# QCopterFC_MCU_Sch.net
KiCad netlist of a schematic drawn in Altium Designer
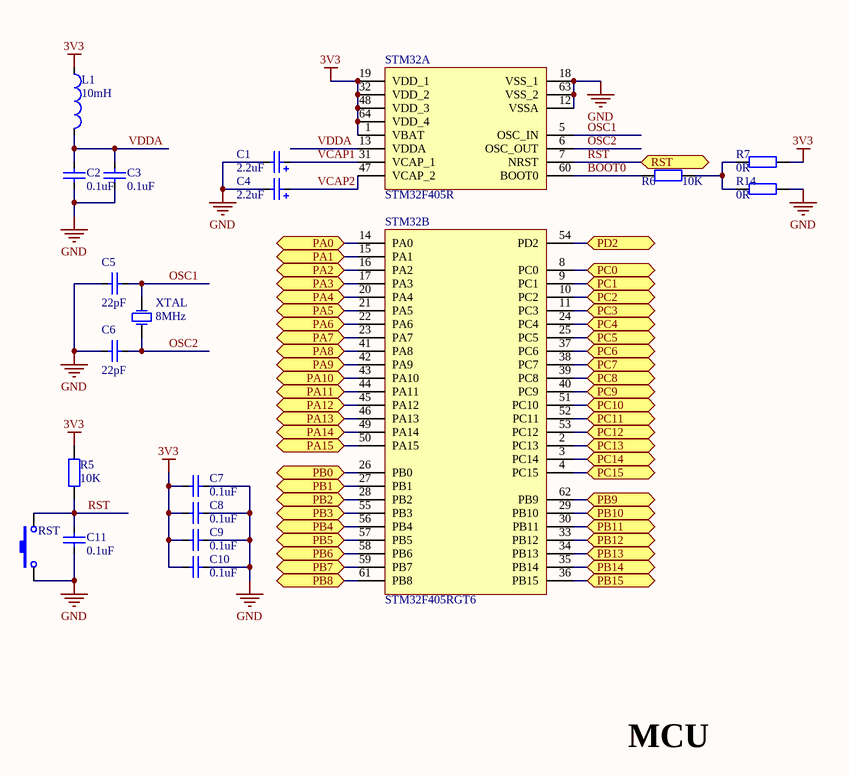
[diagram p0: QCopterFC_MCU_Sch.SchDoc]

(export (version "E")
  (design (tool "Eeschema 10.0.6"))
  (components
    (comp (ref "C1")
      (value "2.2uF")
      (footprint "PCB_Passive:CAP_TAN_P0805")
      (description "Capacitor")
      (fields (field (name "Comment") "Cap_Tan_0805"))
      (libsource (lib "SCH_Passive") (part "Cap_Tan_0805"))
    )
    (comp (ref "C2")
      (value "0.1uF")
      (footprint "PCB_Passive:CAP_0603")
      (description "Capacitor")
      (fields (field (name "Comment") "Cap_0603"))
      (libsource (lib "SCH_Passive") (part "Cap_0603"))
    )
    (comp (ref "C3")
      (value "0.1uF")
      (footprint "PCB_Passive:CAP_0603")
      (description "Capacitor")
      (fields (field (name "Comment") "Cap_0603"))
      (libsource (lib "SCH_Passive") (part "Cap_0603"))
    )
    (comp (ref "C4")
      (value "2.2uF")
      (footprint "PCB_Passive:CAP_TAN_P0805")
      (description "Capacitor")
      (fields (field (name "Comment") "Cap_Tan_0805"))
      (libsource (lib "SCH_Passive") (part "Cap_Tan_0805"))
    )
    (comp (ref "C5")
      (value "22pF")
      (footprint "PCB_Passive:CAP_0603")
      (description "Capacitor")
      (fields (field (name "Comment") "Cap_0603"))
      (libsource (lib "SCH_Passive") (part "Cap_0603"))
    )
    (comp (ref "C6")
      (value "22pF")
      (footprint "PCB_Passive:CAP_0603")
      (description "Capacitor")
      (fields (field (name "Comment") "Cap_0603"))
      (libsource (lib "SCH_Passive") (part "Cap_0603"))
    )
    (comp (ref "C7")
      (value "0.1uF")
      (footprint "PCB_Passive:CAP_0603")
      (description "Capacitor")
      (fields (field (name "Comment") "Cap_0603"))
      (libsource (lib "SCH_Passive") (part "Cap_0603"))
    )
    (comp (ref "C8")
      (value "0.1uF")
      (footprint "PCB_Passive:CAP_0603")
      (description "Capacitor")
      (fields (field (name "Comment") "Cap_0603"))
      (libsource (lib "SCH_Passive") (part "Cap_0603"))
    )
    (comp (ref "C9")
      (value "0.1uF")
      (footprint "PCB_Passive:CAP_0603")
      (description "Capacitor")
      (fields (field (name "Comment") "Cap_0603"))
      (libsource (lib "SCH_Passive") (part "Cap_0603"))
    )
    (comp (ref "C10")
      (value "0.1uF")
      (footprint "PCB_Passive:CAP_0603")
      (description "Capacitor")
      (fields (field (name "Comment") "Cap_0603"))
      (libsource (lib "SCH_Passive") (part "Cap_0603"))
    )
    (comp (ref "C11")
      (value "0.1uF")
      (footprint "PCB_Passive:CAP_0603")
      (description "Capacitor")
      (fields (field (name "Comment") "Cap_0603"))
      (libsource (lib "SCH_Passive") (part "Cap_0603"))
    )
    (comp (ref "L1")
      (value "10mH")
      (footprint "PCB_Passive:IND_0603")
      (description "Inductor")
      (fields (field (name "Comment") "Ind_0603"))
      (libsource (lib "SCH_Passive") (part "Ind_0603"))
    )
    (comp (ref "R5")
      (value "10K")
      (footprint "PCB_Passive:RES_0603")
      (description "Resistor")
      (fields (field (name "Comment") "Res_0603"))
      (libsource (lib "") (part "Res_0603_1"))
    )
    (comp (ref "R6")
      (value "10K")
      (footprint "PCB_Passive:RES_0603")
      (description "Resistor")
      (fields (field (name "Comment") "Res_0603"))
      (libsource (lib "SCH_Passive") (part "Res_0603"))
    )
    (comp (ref "R7")
      (value "0R")
      (footprint "PCB_Passive:RES_0603")
      (description "Resistor")
      (fields (field (name "Comment") "Res_0603"))
      (libsource (lib "SCH_Passive") (part "Res_0603"))
    )
    (comp (ref "R14")
      (value "0R")
      (footprint "PCB_Passive:RES_0603")
      (description "Resistor")
      (fields (field (name "Comment") "Res_0603"))
      (libsource (lib "SCH_Passive") (part "Res_0603"))
    )
    (comp (ref "RST")
      (value "SW-PB_1")
      (footprint "PCB_Switch:BT_90_T")
      (description "Switch")
      (fields (field (name "PUBLISHER") "Altium Limited"))
      (libsource (lib "SCH_Switch") (part "SW-PB_1"))
    )
    (comp (ref "STM32")
      (value "STM32F405R")
      (footprint "PCB_IC:STM32F_64")
      (description "MCU")
      (libsource (lib "SCH_IC") (part "STM32F405R"))
    )
    (comp (ref "XTAL")
      (value "8MHz")
      (footprint "PCB_Oscillator:XTAL_5032")
      (description "Crystal Oscillator")
      (fields (field (name "Comment") "XTAL_5032") (field (name "PUBLISHER") "Altium Limited"))
      (libsource (lib "SCH_Oscillator") (part "XTAL_5032"))
    )
  )
  (nets
    (net (code "1") (name "/BOOT0") (class "Default")
      (node (ref "R6") (pin "1") (pinfunction "1_1") (pintype "passive"))
      (node (ref "STM32") (pin "60") (pinfunction "BOOT0_60") (pintype "passive"))
    )
    (net (code "2") (name "/OSC1") (class "Default")
      (node (ref "C5") (pin "2") (pinfunction "2_2") (pintype "passive"))
      (node (ref "STM32") (pin "5") (pinfunction "OSC_IN_5") (pintype "passive"))
      (node (ref "XTAL") (pin "2") (pinfunction "OSC2_2") (pintype "passive"))
    )
    (net (code "3") (name "/OSC2") (class "Default")
      (node (ref "C6") (pin "2") (pinfunction "2_2") (pintype "passive"))
      (node (ref "STM32") (pin "6") (pinfunction "OSC_OUT_6") (pintype "passive"))
      (node (ref "XTAL") (pin "1") (pinfunction "OSC1_1") (pintype "passive"))
    )
    (net (code "4") (name "/PA0") (class "Default")
      (node (ref "STM32") (pin "14") (pinfunction "PA0_14") (pintype "passive"))
    )
    (net (code "5") (name "/PA1") (class "Default")
      (node (ref "STM32") (pin "15") (pinfunction "PA1_15") (pintype "passive"))
    )
    (net (code "6") (name "/PA2") (class "Default")
      (node (ref "STM32") (pin "16") (pinfunction "PA2_16") (pintype "passive"))
    )
    (net (code "7") (name "/PA3") (class "Default")
      (node (ref "STM32") (pin "17") (pinfunction "PA3_17") (pintype "passive"))
    )
    (net (code "8") (name "/PA4") (class "Default")
      (node (ref "STM32") (pin "20") (pinfunction "PA4_20") (pintype "passive"))
    )
    (net (code "9") (name "/PA5") (class "Default")
      (node (ref "STM32") (pin "21") (pinfunction "PA5_21") (pintype "passive"))
    )
    (net (code "10") (name "/PA6") (class "Default")
      (node (ref "STM32") (pin "22") (pinfunction "PA6_22") (pintype "passive"))
    )
    (net (code "11") (name "/PA7") (class "Default")
      (node (ref "STM32") (pin "23") (pinfunction "PA7_23") (pintype "passive"))
    )
    (net (code "12") (name "/PA8") (class "Default")
      (node (ref "STM32") (pin "41") (pinfunction "PA8_41") (pintype "passive"))
    )
    (net (code "13") (name "/PA9") (class "Default")
      (node (ref "STM32") (pin "42") (pinfunction "PA9_42") (pintype "passive"))
    )
    (net (code "14") (name "/PA10") (class "Default")
      (node (ref "STM32") (pin "43") (pinfunction "PA10_43") (pintype "passive"))
    )
    (net (code "15") (name "/PA11") (class "Default")
      (node (ref "STM32") (pin "44") (pinfunction "PA11_44") (pintype "passive"))
    )
    (net (code "16") (name "/PA12") (class "Default")
      (node (ref "STM32") (pin "45") (pinfunction "PA12_45") (pintype "passive"))
    )
    (net (code "17") (name "/PA13") (class "Default")
      (node (ref "STM32") (pin "46") (pinfunction "PA13_46") (pintype "passive"))
    )
    (net (code "18") (name "/PA14") (class "Default")
      (node (ref "STM32") (pin "49") (pinfunction "PA14_49") (pintype "passive"))
    )
    (net (code "19") (name "/PA15") (class "Default")
      (node (ref "STM32") (pin "50") (pinfunction "PA15_50") (pintype "passive"))
    )
    (net (code "20") (name "/PB0") (class "Default")
      (node (ref "STM32") (pin "26") (pinfunction "PB0_26") (pintype "passive"))
    )
    (net (code "21") (name "/PB1") (class "Default")
      (node (ref "STM32") (pin "27") (pinfunction "PB1_27") (pintype "passive"))
    )
    (net (code "22") (name "/PB2") (class "Default")
      (node (ref "STM32") (pin "28") (pinfunction "PB2_28") (pintype "passive"))
    )
    (net (code "23") (name "/PB3") (class "Default")
      (node (ref "STM32") (pin "55") (pinfunction "PB3_55") (pintype "passive"))
    )
    (net (code "24") (name "/PB4") (class "Default")
      (node (ref "STM32") (pin "56") (pinfunction "PB4_56") (pintype "passive"))
    )
    (net (code "25") (name "/PB5") (class "Default")
      (node (ref "STM32") (pin "57") (pinfunction "PB5_57") (pintype "passive"))
    )
    (net (code "26") (name "/PB6") (class "Default")
      (node (ref "STM32") (pin "58") (pinfunction "PB6_58") (pintype "passive"))
    )
    (net (code "27") (name "/PB7") (class "Default")
      (node (ref "STM32") (pin "59") (pinfunction "PB7_59") (pintype "passive"))
    )
    (net (code "28") (name "/PB8") (class "Default")
      (node (ref "STM32") (pin "61") (pinfunction "PB8_61") (pintype "passive"))
    )
    (net (code "29") (name "/PB9") (class "Default")
      (node (ref "STM32") (pin "62") (pinfunction "PB9_62") (pintype "passive"))
    )
    (net (code "30") (name "/PB10") (class "Default")
      (node (ref "STM32") (pin "29") (pinfunction "PB10_29") (pintype "passive"))
    )
    (net (code "31") (name "/PB11") (class "Default")
      (node (ref "STM32") (pin "30") (pinfunction "PB11_30") (pintype "passive"))
    )
    (net (code "32") (name "/PB12") (class "Default")
      (node (ref "STM32") (pin "33") (pinfunction "PB12_33") (pintype "passive"))
    )
    (net (code "33") (name "/PB13") (class "Default")
      (node (ref "STM32") (pin "34") (pinfunction "PB13_34") (pintype "passive"))
    )
    (net (code "34") (name "/PB14") (class "Default")
      (node (ref "STM32") (pin "35") (pinfunction "PB14_35") (pintype "passive"))
    )
    (net (code "35") (name "/PB15") (class "Default")
      (node (ref "STM32") (pin "36") (pinfunction "PB15_36") (pintype "passive"))
    )
    (net (code "36") (name "/PC0") (class "Default")
      (node (ref "STM32") (pin "8") (pinfunction "PC0_8") (pintype "passive"))
    )
    (net (code "37") (name "/PC1") (class "Default")
      (node (ref "STM32") (pin "9") (pinfunction "PC1_9") (pintype "passive"))
    )
    (net (code "38") (name "/PC2") (class "Default")
      (node (ref "STM32") (pin "10") (pinfunction "PC2_10") (pintype "passive"))
    )
    (net (code "39") (name "/PC3") (class "Default")
      (node (ref "STM32") (pin "11") (pinfunction "PC3_11") (pintype "passive"))
    )
    (net (code "40") (name "/PC4") (class "Default")
      (node (ref "STM32") (pin "24") (pinfunction "PC4_24") (pintype "passive"))
    )
    (net (code "41") (name "/PC5") (class "Default")
      (node (ref "STM32") (pin "25") (pinfunction "PC5_25") (pintype "passive"))
    )
    (net (code "42") (name "/PC6") (class "Default")
      (node (ref "STM32") (pin "37") (pinfunction "PC6_37") (pintype "passive"))
    )
    (net (code "43") (name "/PC7") (class "Default")
      (node (ref "STM32") (pin "38") (pinfunction "PC7_38") (pintype "passive"))
    )
    (net (code "44") (name "/PC8") (class "Default")
      (node (ref "STM32") (pin "39") (pinfunction "PC8_39") (pintype "passive"))
    )
    (net (code "45") (name "/PC9") (class "Default")
      (node (ref "STM32") (pin "40") (pinfunction "PC9_40") (pintype "passive"))
    )
    (net (code "46") (name "/PC10") (class "Default")
      (node (ref "STM32") (pin "51") (pinfunction "PC10_51") (pintype "passive"))
    )
    (net (code "47") (name "/PC11") (class "Default")
      (node (ref "STM32") (pin "52") (pinfunction "PC11_52") (pintype "passive"))
    )
    (net (code "48") (name "/PC12") (class "Default")
      (node (ref "STM32") (pin "53") (pinfunction "PC12_53") (pintype "passive"))
    )
    (net (code "49") (name "/PC13") (class "Default")
      (node (ref "STM32") (pin "2") (pinfunction "PC13_2") (pintype "passive"))
    )
    (net (code "50") (name "/PC14") (class "Default")
      (node (ref "STM32") (pin "3") (pinfunction "PC14_3") (pintype "passive"))
    )
    (net (code "51") (name "/PC15") (class "Default")
      (node (ref "STM32") (pin "4") (pinfunction "PC15_4") (pintype "passive"))
    )
    (net (code "52") (name "/PD2") (class "Default")
      (node (ref "STM32") (pin "54") (pinfunction "PD2_54") (pintype "passive"))
    )
    (net (code "53") (name "/RST") (class "Default")
      (node (ref "C11") (pin "1") (pinfunction "1_1") (pintype "passive"))
      (node (ref "R5") (pin "2") (pinfunction "2_2") (pintype "passive"))
      (node (ref "RST") (pin "2") (pinfunction "2_2") (pintype "passive"))
      (node (ref "STM32") (pin "7") (pinfunction "NRST_7") (pintype "passive"))
    )
    (net (code "54") (name "/VCAP1") (class "Default")
      (node (ref "C1") (pin "1") (pinfunction "1_1") (pintype "passive"))
      (node (ref "STM32") (pin "31") (pinfunction "VCAP_1_31") (pintype "passive"))
    )
    (net (code "55") (name "/VCAP2") (class "Default")
      (node (ref "C4") (pin "1") (pinfunction "1_1") (pintype "passive"))
      (node (ref "STM32") (pin "47") (pinfunction "VCAP_2_47") (pintype "passive"))
    )
    (net (code "56") (name "/VDDA") (class "Default")
      (node (ref "C2") (pin "1") (pinfunction "1_1") (pintype "passive"))
      (node (ref "C3") (pin "1") (pinfunction "1_1") (pintype "passive"))
      (node (ref "L1") (pin "2") (pinfunction "2_2") (pintype "passive"))
      (node (ref "STM32") (pin "13") (pinfunction "VDDA_13") (pintype "passive"))
    )
    (net (code "57") (name "3V3") (class "Default")
      (node (ref "C10") (pin "2") (pinfunction "2_2") (pintype "passive"))
      (node (ref "C7") (pin "2") (pinfunction "2_2") (pintype "passive"))
      (node (ref "C8") (pin "2") (pinfunction "2_2") (pintype "passive"))
      (node (ref "C9") (pin "2") (pinfunction "2_2") (pintype "passive"))
      (node (ref "L1") (pin "1") (pinfunction "1_1") (pintype "passive"))
      (node (ref "R5") (pin "1") (pinfunction "1_1") (pintype "passive"))
      (node (ref "R7") (pin "2") (pinfunction "2_2") (pintype "passive"))
      (node (ref "STM32") (pin "1") (pinfunction "VBAT_1") (pintype "passive"))
      (node (ref "STM32") (pin "19") (pinfunction "VDD_1_19") (pintype "passive"))
      (node (ref "STM32") (pin "32") (pinfunction "VDD_2_32") (pintype "passive"))
      (node (ref "STM32") (pin "48") (pinfunction "VDD_3_48") (pintype "passive"))
      (node (ref "STM32") (pin "64") (pinfunction "VDD_4_64") (pintype "passive"))
    )
    (net (code "58") (name "GND") (class "Default")
      (node (ref "C1") (pin "2") (pinfunction "2_2") (pintype "passive"))
      (node (ref "C10") (pin "1") (pinfunction "1_1") (pintype "passive"))
      (node (ref "C11") (pin "2") (pinfunction "2_2") (pintype "passive"))
      (node (ref "C2") (pin "2") (pinfunction "2_2") (pintype "passive"))
      (node (ref "C3") (pin "2") (pinfunction "2_2") (pintype "passive"))
      (node (ref "C4") (pin "2") (pinfunction "2_2") (pintype "passive"))
      (node (ref "C5") (pin "1") (pinfunction "1_1") (pintype "passive"))
      (node (ref "C6") (pin "1") (pinfunction "1_1") (pintype "passive"))
      (node (ref "C7") (pin "1") (pinfunction "1_1") (pintype "passive"))
      (node (ref "C8") (pin "1") (pinfunction "1_1") (pintype "passive"))
      (node (ref "C9") (pin "1") (pinfunction "1_1") (pintype "passive"))
      (node (ref "R14") (pin "2") (pinfunction "2_2") (pintype "passive"))
      (node (ref "RST") (pin "1") (pinfunction "1_1") (pintype "passive"))
      (node (ref "STM32") (pin "12") (pinfunction "VSSA_12") (pintype "passive"))
      (node (ref "STM32") (pin "18") (pinfunction "VSS_1_18") (pintype "passive"))
      (node (ref "STM32") (pin "63") (pinfunction "VSS_2_63") (pintype "passive"))
    )
    (net (code "59") (name "Net-(R14-Pad1)") (class "Default")
      (node (ref "R14") (pin "1") (pinfunction "1_1") (pintype "passive"))
      (node (ref "R6") (pin "2") (pinfunction "2_2") (pintype "passive"))
      (node (ref "R7") (pin "1") (pinfunction "1_1") (pintype "passive"))
    )
  )
)
